# Booster_USER_IFC_ENC424J600.net
KiCad netlist of a schematic drawn in Altium Designer
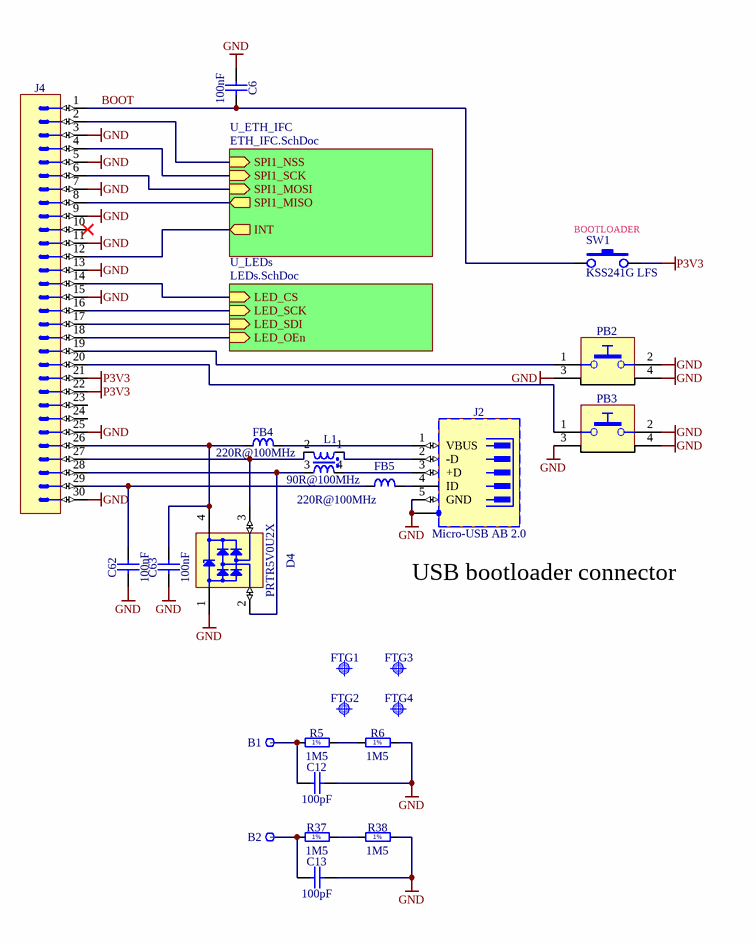
[diagram p0: Booster_USER_IFC_ENC424J600.SchDoc]

(export (version "E")
  (design (tool "Eeschema 10.0.6"))
  (components
    (comp (ref "B1")
      (value "Plated Hole")
      (footprint "MTG320_550")
      (description "Single Terminal Socket")
      (fields (field (name "PART NUMBER") "PLATED_HOLE3.2_PAD5.5") (field (name "AUTHOR") "CERN DEM JMW"))
      (libsource (lib "Eletro-mechanical") (part "Single Terminal Socket"))
    )
    (comp (ref "B2")
      (value "Plated Hole")
      (footprint "MTG320_550")
      (description "Single Terminal Socket")
      (fields (field (name "PART NUMBER") "PLATED_HOLE3.2_PAD5.5") (field (name "AUTHOR") "CERN DEM JMW"))
      (libsource (lib "Eletro-mechanical") (part "Single Terminal Socket"))
    )
    (comp (ref "C6")
      (value "100nF")
      (footprint "CAPC1005X55N")
      (description "Non-polarised capacitor")
      (fields
        (field (name "PART NUMBER") "CC0402_100NF_16V_10%_X7R")
        (field (name "VOLTAGE") "16V")
        (field (name "AUTHOR") "CERN DEM JLC")
      )
      (libsource (lib "Capacitors") (part "Capacitor - non polarized"))
    )
    (comp (ref "C12")
      (value "100pF")
      (footprint "CAPC2012X88N")
      (description "Non-polarised capacitor")
      (fields
        (field (name "PART NUMBER") "CC0805_100PF_200V_5%_C0G")
        (field (name "VOLTAGE") "200V")
        (field (name "AUTHOR") "CERN DEM JLC")
      )
      (libsource (lib "Capacitors") (part "Capacitor - non polarized"))
    )
    (comp (ref "C13")
      (value "100pF")
      (footprint "CAPC2012X88N")
      (description "Non-polarised capacitor")
      (fields
        (field (name "PART NUMBER") "CC0805_100PF_200V_5%_C0G")
        (field (name "VOLTAGE") "200V")
        (field (name "AUTHOR") "CERN DEM JLC")
      )
      (libsource (lib "Capacitors") (part "Capacitor - non polarized"))
    )
    (comp (ref "C62")
      (value "100nF")
      (footprint "CAPC1005X55N")
      (description "Non-polarised capacitor")
      (fields
        (field (name "PART NUMBER") "CC0402_100NF_16V_10%_X7R")
        (field (name "VOLTAGE") "16V")
        (field (name "AUTHOR") "CERN DEM JLC")
      )
      (libsource (lib "Capacitors") (part "Capacitor - non polarized"))
    )
    (comp (ref "C63")
      (value "100nF")
      (footprint "CAPC1005X55N")
      (description "Non-polarised capacitor")
      (fields
        (field (name "PART NUMBER") "CC0402_100NF_16V_10%_X7R")
        (field (name "VOLTAGE") "16V")
        (field (name "AUTHOR") "CERN DEM JLC")
      )
      (libsource (lib "Capacitors") (part "Capacitor - non polarized"))
    )
    (comp (ref "D4")
      (value "PRTR5V0U2X")
      (footprint "SOT190P230X110-4N")
      (description "Ultra Low Capacitance Double Rail-to-Rail ESD Protection Diode")
      (fields
        (field (name "VOLTAGE") "5.5V")
        (field (name "MANUFACTURER") "NXP SEMICONDUCTORS")
        (field (name "AUTHOR") "CERN DEM JLC")
      )
      (libsource (lib "ICs And Semiconductors") (part "PRTR5V0U2X"))
    )
    (comp (ref "FB4")
      (value "220R@100MHz")
      (footprint "INDC2012X105N")
      (description "Inductor")
      (fields
        (field (name "PART NUMBER") "IND0805_MURATA_BLM21PG221SN1D")
        (field (name "POWER") "2A")
        (field (name "AUTHOR") "CERN DEM JLC")
      )
      (libsource (lib "Inductors & Transformers") (part "Inductor"))
    )
    (comp (ref "FB5")
      (value "220R@100MHz")
      (footprint "INDC2012X105N")
      (description "Inductor")
      (fields
        (field (name "PART NUMBER") "IND0805_MURATA_BLM21PG221SN1D")
        (field (name "POWER") "2A")
        (field (name "AUTHOR") "CERN DEM JLC")
      )
      (libsource (lib "Inductors & Transformers") (part "Inductor"))
    )
    (comp (ref "FTG1")
      (value "Use only in PCB")
      (footprint "FIDUCIAL_TOP_C100-200")
      (description "Fiducial Target")
      (fields (field (name "PART NUMBER") "FIDUCIAL_TARGET_C100-200") (field (name "AUTHOR") "CERN DEM JLC"))
      (libsource (lib "Eletro-mechanical") (part "Fiducial Target"))
    )
    (comp (ref "FTG2")
      (value "Use only in PCB")
      (footprint "FIDUCIAL_TOP_S100-200")
      (description "Fiducial Target")
      (fields (field (name "PART NUMBER") "FIDUCIAL_TARGET_S100-200") (field (name "AUTHOR") "CERN DEM JLC"))
      (libsource (lib "Eletro-mechanical") (part "Fiducial Target"))
    )
    (comp (ref "FTG3")
      (value "Use only in PCB")
      (footprint "FIDUCIAL_TOP_C100-200")
      (description "Fiducial Target")
      (fields (field (name "PART NUMBER") "FIDUCIAL_TARGET_C100-200") (field (name "AUTHOR") "CERN DEM JLC"))
      (libsource (lib "Eletro-mechanical") (part "Fiducial Target"))
    )
    (comp (ref "FTG4")
      (value "Use only in PCB")
      (footprint "FIDUCIAL_TOP_S100-200")
      (description "Fiducial Target")
      (fields (field (name "PART NUMBER") "FIDUCIAL_TARGET_S100-200") (field (name "AUTHOR") "CERN DEM JLC"))
      (libsource (lib "Eletro-mechanical") (part "Fiducial Target"))
    )
    (comp (ref "J2")
      (value "Micro-USB AB 2.0")
      (footprint "HIROSE_ZX62RD-AB-5P8")
      (description "5 Pin + 1 Shield USB Receptacle")
      (fields
        (field (name "PART NUMBER") "HIROSE_ZX62RD-AB-5P8")
        (field (name "MANUFACTURER") "HIROSE (HRS)")
        (field (name "AUTHOR") "CERN DEM JLC")
      )
      (libsource (lib "Connectors") (part "Connector USB 5 Pin + 1Shield"))
    )
    (comp (ref "J4")
      (value "~")
      (footprint "3M_N2530-6002RB")
      (description "Connector 30 Male")
      (fields
        (field (name "PART NUMBER") "3M_N2530-6002RB")
        (field (name "MANUFACTURER") "3M")
        (field (name "AUTHOR") "CERN DEM JLC")
      )
      (libsource (lib "Connectors") (part "Connector 30 Male"))
    )
    (comp (ref "L1")
      (value "90R@100MHz")
      (footprint "IND_MURATA_DLW21S")
      (description "Inductor Common Mode")
      (fields
        (field (name "PART NUMBER") "IND_MURATA_DLW21SN900SQ2L")
        (field (name "POWER") "330mA")
        (field (name "AUTHOR") "CERN DEM JLC")
      )
      (libsource (lib "Inductors & Transformers") (part "Inductor Common Mode 1Dot-2 4Dot-3"))
    )
    (comp (ref "PB2")
      (value "Push Button")
      (footprint "PB_TYCO_1-1825027-1")
      (description "Push-Button Switch SPDT")
      (fields
        (field (name "PART NUMBER") "PB_TYCO_1-1825027-1")
        (field (name "MANUFACTURER") "TYCO ELECTRONICS")
        (field (name "AUTHOR") "CERN DEM JLC")
      )
      (libsource (lib "Eletro-mechanical") (part "PB SPST 1NO-2NO 34CASE"))
    )
    (comp (ref "PB3")
      (value "Push Button")
      (footprint "PB_TYCO_1-1825027-1")
      (description "Push-Button Switch SPDT")
      (fields
        (field (name "PART NUMBER") "PB_TYCO_1-1825027-1")
        (field (name "MANUFACTURER") "TYCO ELECTRONICS")
        (field (name "AUTHOR") "CERN DEM JLC")
      )
      (libsource (lib "Eletro-mechanical") (part "PB SPST 1NO-2NO 34CASE"))
    )
    (comp (ref "R5")
      (value "1M5")
      (footprint "RESC1005X40N")
      (description "Resistor - 1%")
      (fields
        (field (name "PART NUMBER") "R0402_1M5_1%_0.0625W_100PPM")
        (field (name "POWER") "0.0625W")
        (field (name "AUTHOR") "CERN DEM JLC")
      )
      (libsource (lib "Resistors") (part "Resistor - 1%"))
    )
    (comp (ref "R6")
      (value "1M5")
      (footprint "RESC1005X40N")
      (description "Resistor - 1%")
      (fields
        (field (name "PART NUMBER") "R0402_1M5_1%_0.0625W_100PPM")
        (field (name "POWER") "0.0625W")
        (field (name "AUTHOR") "CERN DEM JLC")
      )
      (libsource (lib "Resistors") (part "Resistor - 1%"))
    )
    (comp (ref "R37")
      (value "1M5")
      (footprint "RESC1005X40N")
      (description "Resistor - 1%")
      (fields
        (field (name "PART NUMBER") "R0402_1M5_1%_0.0625W_100PPM")
        (field (name "POWER") "0.0625W")
        (field (name "AUTHOR") "CERN DEM JLC")
      )
      (libsource (lib "Resistors") (part "Resistor - 1%"))
    )
    (comp (ref "R38")
      (value "1M5")
      (footprint "RESC1005X40N")
      (description "Resistor - 1%")
      (fields
        (field (name "PART NUMBER") "R0402_1M5_1%_0.0625W_100PPM")
        (field (name "POWER") "0.0625W")
        (field (name "AUTHOR") "CERN DEM JLC")
      )
      (libsource (lib "Resistors") (part "Resistor - 1%"))
    )
    (comp (ref "SW1")
      (value "KSS241G LFS")
      (footprint "KSS241G LFS")
      (description "Push button")
      (libsource (lib "LIBRARY_SCH") (part "SW-TACT_SMD_RA_mini"))
    )
  )
  (nets
    (net (code "1") (name "/BOOT") (class "Default")
      (node (ref "C6") (pin "2") (pinfunction "2_2") (pintype "passive"))
      (node (ref "J4") (pin "1") (pinfunction "1_1") (pintype "bidirectional"))
      (node (ref "SW1") (pin "1") (pinfunction "1_1") (pintype "passive"))
    )
    (net (code "2") (name "/INT") (class "Default")
      (node (ref "J4") (pin "12") (pinfunction "12_12") (pintype "bidirectional"))
    )
    (net (code "3") (name "/LED_CS") (class "Default")
      (node (ref "J4") (pin "14") (pinfunction "14_14") (pintype "bidirectional"))
    )
    (net (code "4") (name "/LED_OEn") (class "Default")
      (node (ref "J4") (pin "18") (pinfunction "18_18") (pintype "bidirectional"))
    )
    (net (code "5") (name "/LED_SCK") (class "Default")
      (node (ref "J4") (pin "16") (pinfunction "16_16") (pintype "bidirectional"))
    )
    (net (code "6") (name "/LED_SDI") (class "Default")
      (node (ref "J4") (pin "17") (pinfunction "17_17") (pintype "bidirectional"))
    )
    (net (code "7") (name "/SPI1_MISO") (class "Default")
      (node (ref "J4") (pin "8") (pinfunction "8_8") (pintype "bidirectional"))
    )
    (net (code "8") (name "/SPI1_MOSI") (class "Default")
      (node (ref "J4") (pin "6") (pinfunction "6_6") (pintype "bidirectional"))
    )
    (net (code "9") (name "/SPI1_NSS") (class "Default")
      (node (ref "J4") (pin "2") (pinfunction "2_2") (pintype "bidirectional"))
    )
    (net (code "10") (name "/SPI1_SCK") (class "Default")
      (node (ref "J4") (pin "4") (pinfunction "4_4") (pintype "bidirectional"))
    )
    (net (code "11") (name "GND") (class "Default")
      (node (ref "C12") (pin "2") (pinfunction "2_2") (pintype "passive"))
      (node (ref "C13") (pin "2") (pinfunction "2_2") (pintype "passive"))
      (node (ref "C6") (pin "1") (pinfunction "1_1") (pintype "passive"))
      (node (ref "C62") (pin "1") (pinfunction "1_1") (pintype "passive"))
      (node (ref "C63") (pin "1") (pinfunction "1_1") (pintype "passive"))
      (node (ref "D4") (pin "1") (pinfunction "GND_1") (pintype "power_in"))
      (node (ref "J2") (pin "5") (pinfunction "GND_5") (pintype "bidirectional"))
      (node (ref "J2") (pin "6") (pinfunction "SH_6") (pintype "power_in"))
      (node (ref "J4") (pin "11") (pinfunction "11_11") (pintype "bidirectional"))
      (node (ref "J4") (pin "13") (pinfunction "13_13") (pintype "bidirectional"))
      (node (ref "J4") (pin "15") (pinfunction "15_15") (pintype "bidirectional"))
      (node (ref "J4") (pin "25") (pinfunction "25_25") (pintype "bidirectional"))
      (node (ref "J4") (pin "3") (pinfunction "3_3") (pintype "bidirectional"))
      (node (ref "J4") (pin "30") (pinfunction "30_30") (pintype "bidirectional"))
      (node (ref "J4") (pin "5") (pinfunction "5_5") (pintype "bidirectional"))
      (node (ref "J4") (pin "7") (pinfunction "7_7") (pintype "bidirectional"))
      (node (ref "J4") (pin "9") (pinfunction "9_9") (pintype "bidirectional"))
      (node (ref "PB2") (pin "2") (pinfunction "2_2") (pintype "passive"))
      (node (ref "PB2") (pin "3") (pinfunction "3_3") (pintype "passive"))
      (node (ref "PB2") (pin "4") (pinfunction "4_4") (pintype "passive"))
      (node (ref "PB3") (pin "2") (pinfunction "2_2") (pintype "passive"))
      (node (ref "PB3") (pin "3") (pinfunction "3_3") (pintype "passive"))
      (node (ref "PB3") (pin "4") (pinfunction "4_4") (pintype "passive"))
      (node (ref "R38") (pin "2") (pinfunction "2_2") (pintype "passive"))
      (node (ref "R6") (pin "2") (pinfunction "2_2") (pintype "passive"))
    )
    (net (code "12") (name "Net-(B1-Pad1)") (class "Default")
      (node (ref "B1") (pin "1") (pinfunction "1_1") (pintype "bidirectional"))
      (node (ref "C12") (pin "1") (pinfunction "1_1") (pintype "passive"))
      (node (ref "R5") (pin "1") (pinfunction "1_1") (pintype "passive"))
    )
    (net (code "13") (name "Net-(B2-Pad1)") (class "Default")
      (node (ref "B2") (pin "1") (pinfunction "1_1") (pintype "bidirectional"))
      (node (ref "C13") (pin "1") (pinfunction "1_1") (pintype "passive"))
      (node (ref "R37") (pin "1") (pinfunction "1_1") (pintype "passive"))
    )
    (net (code "14") (name "Net-(C62-Pad2)") (class "Default")
      (node (ref "C62") (pin "2") (pinfunction "2_2") (pintype "passive"))
      (node (ref "FB5") (pin "1") (pinfunction "1_1") (pintype "passive"))
      (node (ref "J4") (pin "29") (pinfunction "29_29") (pintype "bidirectional"))
    )
    (net (code "15") (name "Net-(D4-I{slash}O1)") (class "Default")
      (node (ref "D4") (pin "2") (pinfunction "I/O1_2") (pintype "bidirectional"))
      (node (ref "J4") (pin "28") (pinfunction "28_28") (pintype "bidirectional"))
      (node (ref "L1") (pin "3") (pinfunction "3_3") (pintype "passive"))
    )
    (net (code "16") (name "Net-(D4-I{slash}O2)") (class "Default")
      (node (ref "D4") (pin "3") (pinfunction "I/O2_3") (pintype "bidirectional"))
      (node (ref "J4") (pin "27") (pinfunction "27_27") (pintype "bidirectional"))
      (node (ref "L1") (pin "2") (pinfunction "2_2") (pintype "passive"))
    )
    (net (code "17") (name "Net-(D4-VCC)") (class "Default")
      (node (ref "C63") (pin "2") (pinfunction "2_2") (pintype "passive"))
      (node (ref "D4") (pin "4") (pinfunction "VCC_4") (pintype "power_in"))
      (node (ref "FB4") (pin "1") (pinfunction "1_1") (pintype "passive"))
      (node (ref "J4") (pin "26") (pinfunction "26_26") (pintype "bidirectional"))
    )
    (net (code "18") (name "Net-(J2-+D)") (class "Default")
      (node (ref "J2") (pin "3") (pinfunction "+D_3") (pintype "bidirectional"))
      (node (ref "L1") (pin "4") (pinfunction "4_4") (pintype "passive"))
    )
    (net (code "19") (name "Net-(J2--D)") (class "Default")
      (node (ref "J2") (pin "2") (pinfunction "-D_2") (pintype "bidirectional"))
      (node (ref "L1") (pin "1") (pinfunction "1_1") (pintype "passive"))
    )
    (net (code "20") (name "Net-(J2-ID)") (class "Default")
      (node (ref "FB5") (pin "2") (pinfunction "2_2") (pintype "passive"))
      (node (ref "J2") (pin "4") (pinfunction "ID_4") (pintype "passive"))
    )
    (net (code "21") (name "Net-(J2-VBUS)") (class "Default")
      (node (ref "FB4") (pin "2") (pinfunction "2_2") (pintype "passive"))
      (node (ref "J2") (pin "1") (pinfunction "VBUS_1") (pintype "bidirectional"))
    )
    (net (code "22") (name "Net-(J4-Pad19)") (class "Default")
      (node (ref "J4") (pin "19") (pinfunction "19_19") (pintype "bidirectional"))
      (node (ref "PB2") (pin "1") (pinfunction "1_1") (pintype "passive"))
    )
    (net (code "23") (name "Net-(J4-Pad20)") (class "Default")
      (node (ref "J4") (pin "20") (pinfunction "20_20") (pintype "bidirectional"))
      (node (ref "PB3") (pin "1") (pinfunction "1_1") (pintype "passive"))
    )
    (net (code "24") (name "Net-(R5-Pad2)") (class "Default")
      (node (ref "R5") (pin "2") (pinfunction "2_2") (pintype "passive"))
      (node (ref "R6") (pin "1") (pinfunction "1_1") (pintype "passive"))
    )
    (net (code "25") (name "Net-(R37-Pad2)") (class "Default")
      (node (ref "R37") (pin "2") (pinfunction "2_2") (pintype "passive"))
      (node (ref "R38") (pin "1") (pinfunction "1_1") (pintype "passive"))
    )
    (net (code "26") (name "P3V3") (class "Default")
      (node (ref "J4") (pin "21") (pinfunction "21_21") (pintype "bidirectional"))
      (node (ref "J4") (pin "22") (pinfunction "22_22") (pintype "bidirectional"))
      (node (ref "SW1") (pin "2") (pinfunction "2_2") (pintype "passive"))
    )
    (net (code "27") (name "unconnected-(J4-Pad10)") (class "Default")
      (node (ref "J4") (pin "10") (pinfunction "10_10") (pintype "bidirectional+no_connect"))
    )
    (net (code "28") (name "unconnected-(J4-Pad23)") (class "Default")
      (node (ref "J4") (pin "23") (pinfunction "23_23") (pintype "bidirectional"))
    )
    (net (code "29") (name "unconnected-(J4-Pad24)") (class "Default")
      (node (ref "J4") (pin "24") (pinfunction "24_24") (pintype "bidirectional"))
    )
  )
)
